# riffleito-KAP-REVA.net
KiCad netlist of a schematic drawn in EAGLE
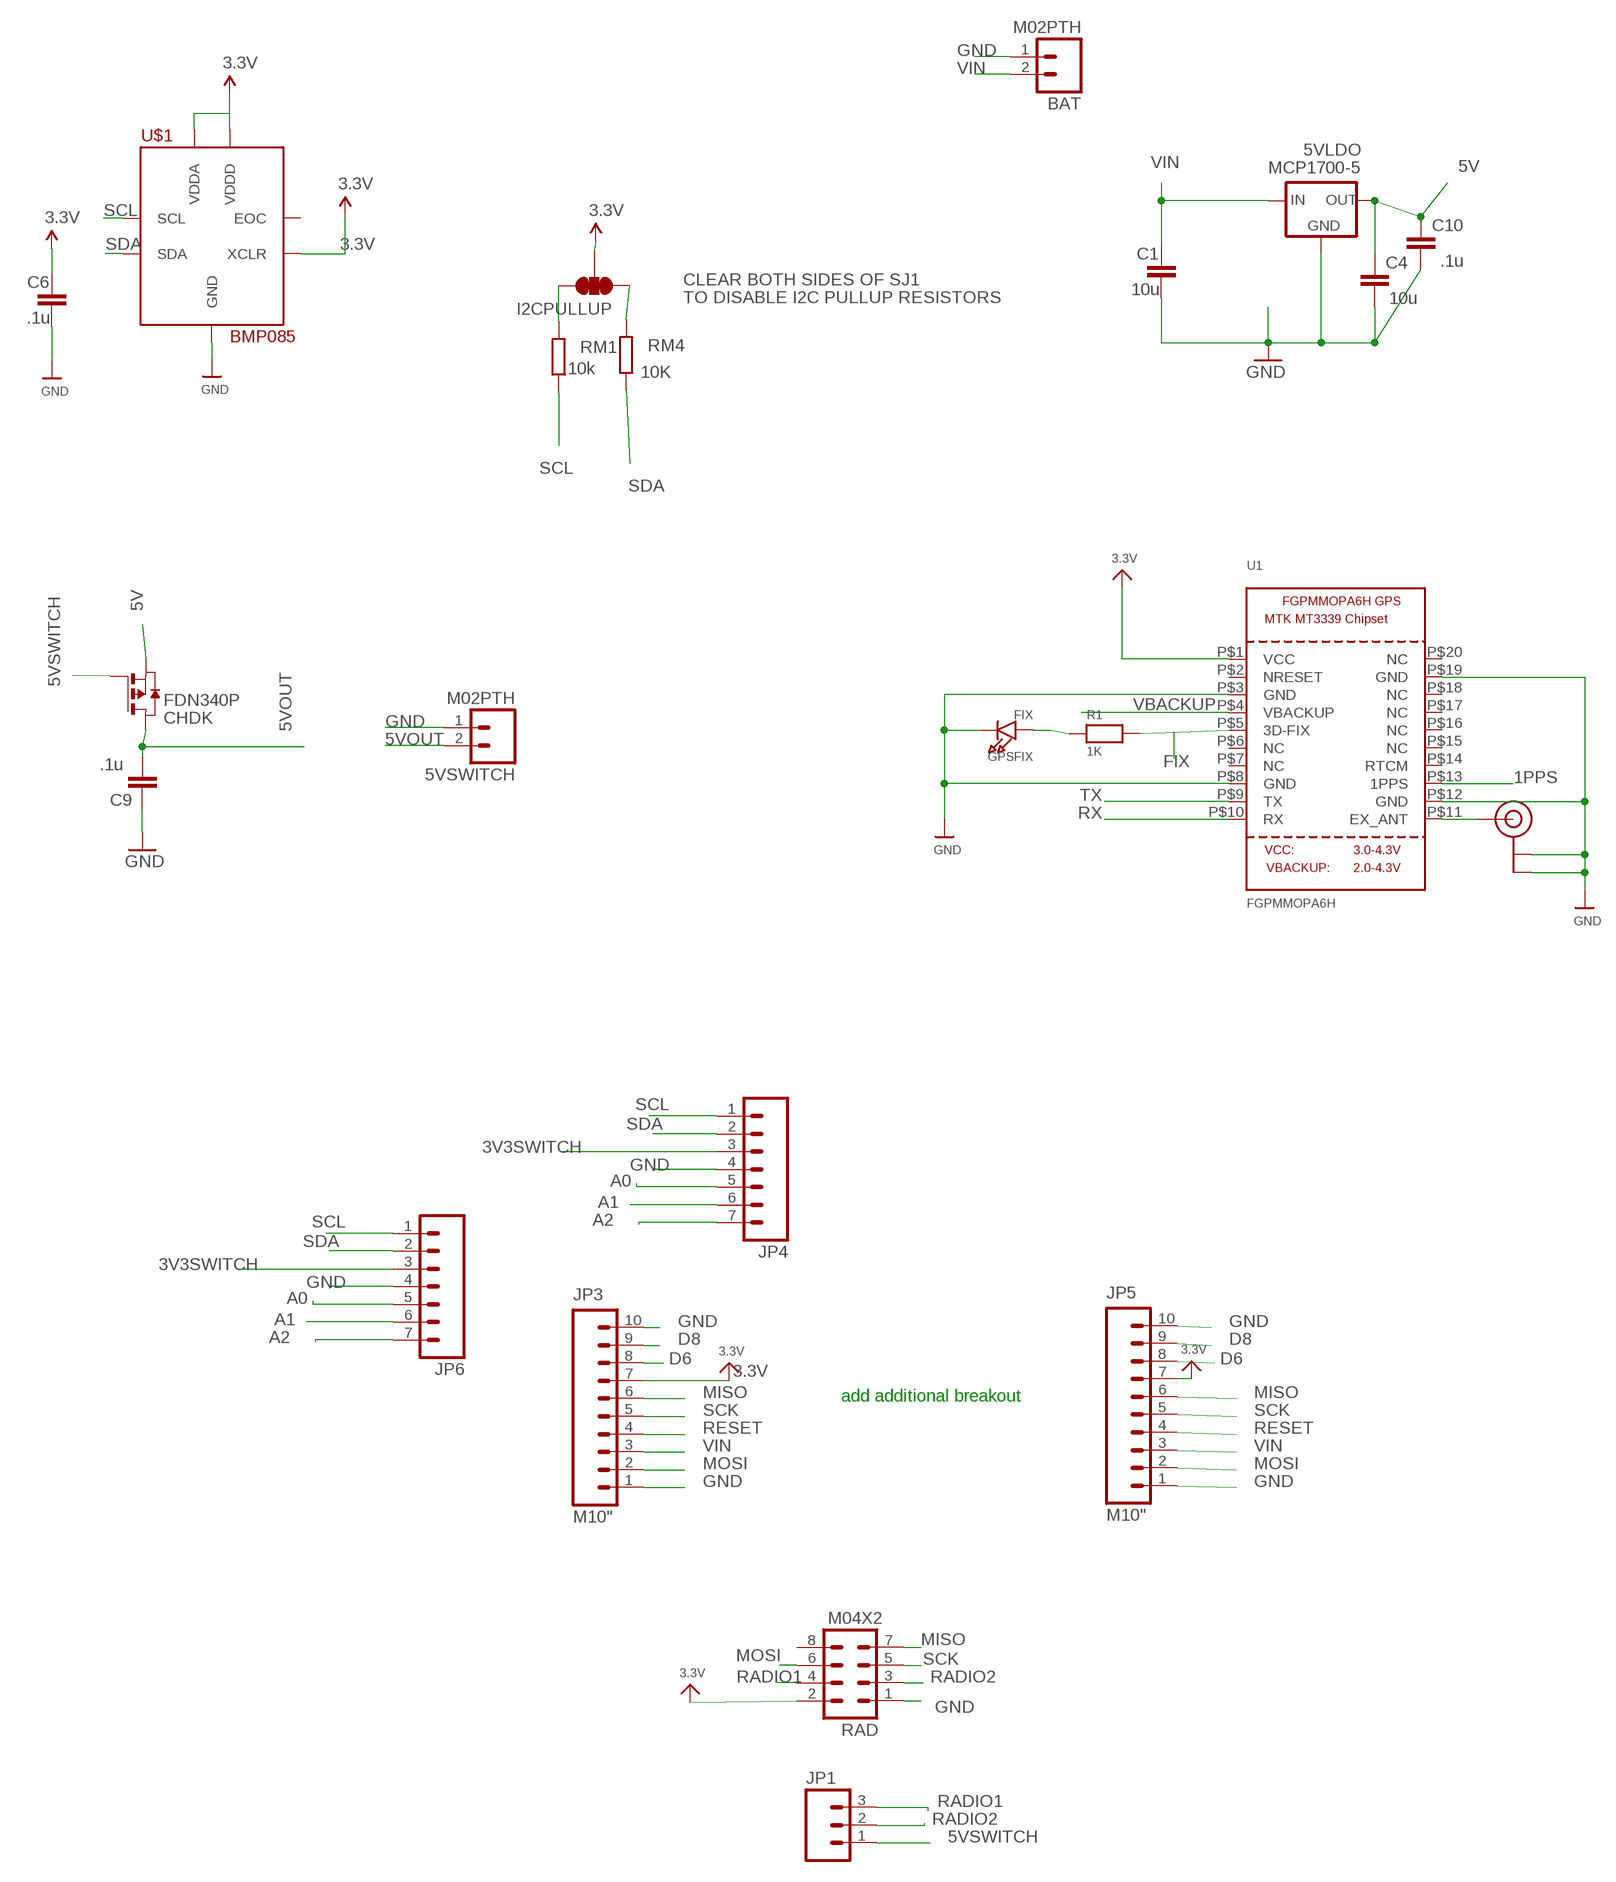
[diagram p0: schematic, sheet 1]

(export (version "E")
  (design (tool "Eeschema 10.0.6"))
  (components
    (comp (ref "5VLDO")
      (value "MCP1700-5")
      (footprint "eagle-import:SOT23")
      (libsource (lib "eagle-import") (part "MCP1700SOT233"))
    )
    (comp (ref "5VSWITCH")
      (value "M02PTH")
      (footprint "eagle-import:1X02")
      (libsource (lib "eagle-import") (part "M02PTH"))
    )
    (comp (ref "BAT")
      (value "M02PTH")
      (footprint "eagle-import:1X02")
      (libsource (lib "eagle-import") (part "M02PTH"))
    )
    (comp (ref "C1")
      (value "10u")
      (footprint "eagle-import:C0805")
      (libsource (lib "eagle-import") (part "C-EUC0805"))
    )
    (comp (ref "C4")
      (value "10u")
      (footprint "eagle-import:C0805")
      (libsource (lib "eagle-import") (part "C-EUC0805"))
    )
    (comp (ref "C6")
      (value ".1u")
      (footprint "eagle-import:C0805")
      (libsource (lib "eagle-import") (part "C-EUC0805"))
    )
    (comp (ref "C9")
      (value ".1u")
      (footprint "eagle-import:C0805")
      (libsource (lib "eagle-import") (part "C-EUC0805"))
    )
    (comp (ref "C10")
      (value ".1u")
      (footprint "eagle-import:C0805")
      (libsource (lib "eagle-import") (part "C-EUC0805"))
    )
    (comp (ref "CHDK")
      (value "FDN340P")
      (footprint "eagle-import:SOT-23")
      (libsource (lib "eagle-import") (part "PMOSSOT23"))
    )
    (comp (ref "GPSFIX")
      (value "FIX")
      (footprint "eagle-import:CHIPLED_0805")
      (libsource (lib "eagle-import") (part "LED0805"))
    )
    (comp (ref "I2CPULLUP")
      (value "SOLDERJUMPER_2WAYPASTE1&2&3")
      (footprint "eagle-import:SJ_3_PASTE1&2&3")
      (libsource (lib "eagle-import") (part "SOLDERJUMPER_2WAYPASTE1&2&3"))
    )
    (comp (ref "JP1")
      (value "M03PTH")
      (footprint "eagle-import:1X03")
      (libsource (lib "eagle-import") (part "M03PTH"))
    )
    (comp (ref "JP3")
      (value "M10\"")
      (footprint "eagle-import:1X10")
      (libsource (lib "eagle-import") (part "M10{dblquote}"))
    )
    (comp (ref "JP4")
      (value "M07")
      (footprint "eagle-import:1X07")
      (libsource (lib "eagle-import") (part "M07"))
    )
    (comp (ref "JP5")
      (value "M10\"")
      (footprint "eagle-import:1X10")
      (libsource (lib "eagle-import") (part "M10{dblquote}"))
    )
    (comp (ref "JP6")
      (value "M07")
      (footprint "eagle-import:1X07")
      (libsource (lib "eagle-import") (part "M07"))
    )
    (comp (ref "R1")
      (value "1K")
      (footprint "eagle-import:0805")
      (libsource (lib "eagle-import") (part "RESISTOR0805"))
    )
    (comp (ref "RAD")
      (value "M04X2")
      (footprint "eagle-import:2X4")
      (libsource (lib "eagle-import") (part "M04X2"))
    )
    (comp (ref "RM1")
      (value "10k")
      (footprint "eagle-import:R0805")
      (libsource (lib "eagle-import") (part "R-EU_R0805"))
    )
    (comp (ref "RM4")
      (value "10K")
      (footprint "eagle-import:R0805")
      (libsource (lib "eagle-import") (part "R-EU_R0805"))
    )
    (comp (ref "U$1")
      (value "BMP085")
      (footprint "eagle-import:BMP085")
      (libsource (lib "eagle-import") (part "BMP085"))
    )
    (comp (ref "U$20")
      (value "U.FL")
      (footprint "eagle-import:U.FL")
      (libsource (lib "eagle-import") (part "U.FL"))
    )
    (comp (ref "U1")
      (value "FGPMMOPA6H")
      (footprint "eagle-import:FGPMMOPA6H")
      (libsource (lib "eagle-import") (part "GPS_FGPMMOPA6H"))
    )
  )
  (nets
    (net (code "1") (name "/1PPS") (class "Default")
      (node (ref "U1") (pin "P$13") (pinfunction "1PPS_P$13") (pintype "bidirectional"))
    )
    (net (code "2") (name "/3V3SWITCH") (class "Default")
      (node (ref "JP4") (pin "3") (pinfunction "3_3") (pintype "passive"))
      (node (ref "JP6") (pin "3") (pinfunction "3_3") (pintype "passive"))
    )
    (net (code "3") (name "/5V") (class "Default")
      (node (ref "5VLDO") (pin "2") (pinfunction "OUT_2") (pintype "passive"))
      (node (ref "C10") (pin "1") (pinfunction "1_1") (pintype "passive"))
      (node (ref "C4") (pin "1") (pinfunction "1_1") (pintype "passive"))
      (node (ref "CHDK") (pin "2") (pinfunction "S_2") (pintype "passive"))
    )
    (net (code "4") (name "/5VOUT") (class "Default")
      (node (ref "5VSWITCH") (pin "2") (pinfunction "2_2") (pintype "passive"))
      (node (ref "C9") (pin "2") (pinfunction "2_2") (pintype "passive"))
      (node (ref "CHDK") (pin "1") (pinfunction "D_1") (pintype "passive"))
    )
    (net (code "5") (name "/5VSWITCH") (class "Default")
      (node (ref "CHDK") (pin "3") (pinfunction "G_3") (pintype "passive"))
      (node (ref "JP1") (pin "1") (pinfunction "1_1") (pintype "passive"))
    )
    (net (code "6") (name "/A0") (class "Default")
      (node (ref "JP4") (pin "5") (pinfunction "5_5") (pintype "passive"))
      (node (ref "JP6") (pin "5") (pinfunction "5_5") (pintype "passive"))
    )
    (net (code "7") (name "/A1") (class "Default")
      (node (ref "JP4") (pin "6") (pinfunction "6_6") (pintype "passive"))
      (node (ref "JP6") (pin "6") (pinfunction "6_6") (pintype "passive"))
    )
    (net (code "8") (name "/A2") (class "Default")
      (node (ref "JP4") (pin "7") (pinfunction "7_7") (pintype "passive"))
      (node (ref "JP6") (pin "7") (pinfunction "7_7") (pintype "passive"))
    )
    (net (code "9") (name "/D6") (class "Default")
      (node (ref "JP3") (pin "8") (pinfunction "8_8") (pintype "passive"))
      (node (ref "JP5") (pin "8") (pinfunction "8_8") (pintype "passive"))
    )
    (net (code "10") (name "/D8") (class "Default")
      (node (ref "JP3") (pin "9") (pinfunction "9_9") (pintype "passive"))
      (node (ref "JP5") (pin "9") (pinfunction "9_9") (pintype "passive"))
    )
    (net (code "12") (name "/MISO") (class "Default")
      (node (ref "JP3") (pin "6") (pinfunction "6_6") (pintype "passive"))
      (node (ref "JP5") (pin "6") (pinfunction "6_6") (pintype "passive"))
      (node (ref "RAD") (pin "7") (pinfunction "7_7") (pintype "passive"))
    )
    (net (code "13") (name "/MOSI") (class "Default")
      (node (ref "JP3") (pin "2") (pinfunction "2_2") (pintype "passive"))
      (node (ref "JP5") (pin "2") (pinfunction "2_2") (pintype "passive"))
      (node (ref "RAD") (pin "6") (pinfunction "6_6") (pintype "passive"))
    )
    (net (code "14") (name "/RADIO1") (class "Default")
      (node (ref "JP1") (pin "3") (pinfunction "3_3") (pintype "passive"))
      (node (ref "RAD") (pin "4") (pinfunction "4_4") (pintype "passive"))
    )
    (net (code "15") (name "/RADIO2") (class "Default")
      (node (ref "JP1") (pin "2") (pinfunction "2_2") (pintype "passive"))
      (node (ref "RAD") (pin "3") (pinfunction "3_3") (pintype "passive"))
    )
    (net (code "16") (name "/RESET") (class "Default")
      (node (ref "JP3") (pin "4") (pinfunction "4_4") (pintype "passive"))
      (node (ref "JP5") (pin "4") (pinfunction "4_4") (pintype "passive"))
    )
    (net (code "17") (name "/RX") (class "Default")
      (node (ref "U1") (pin "P$10") (pinfunction "RX_P$10") (pintype "bidirectional"))
    )
    (net (code "18") (name "/SCK") (class "Default")
      (node (ref "JP3") (pin "5") (pinfunction "5_5") (pintype "passive"))
      (node (ref "JP5") (pin "5") (pinfunction "5_5") (pintype "passive"))
      (node (ref "RAD") (pin "5") (pinfunction "5_5") (pintype "passive"))
    )
    (net (code "19") (name "/SCL") (class "Default")
      (node (ref "JP4") (pin "1") (pinfunction "1_1") (pintype "passive"))
      (node (ref "JP6") (pin "1") (pinfunction "1_1") (pintype "passive"))
      (node (ref "RM1") (pin "1") (pinfunction "1_1") (pintype "passive"))
      (node (ref "U$1") (pin "P$6") (pinfunction "SCL_P$6") (pintype "bidirectional"))
    )
    (net (code "20") (name "/SDA") (class "Default")
      (node (ref "JP4") (pin "2") (pinfunction "2_2") (pintype "passive"))
      (node (ref "JP6") (pin "2") (pinfunction "2_2") (pintype "passive"))
      (node (ref "RM4") (pin "1") (pinfunction "1_1") (pintype "passive"))
      (node (ref "U$1") (pin "P$7") (pinfunction "SDA_P$7") (pintype "bidirectional"))
    )
    (net (code "21") (name "/TX") (class "Default")
      (node (ref "U1") (pin "P$9") (pinfunction "TX_P$9") (pintype "bidirectional"))
    )
    (net (code "22") (name "/VBACKUP") (class "Default")
      (node (ref "U1") (pin "P$4") (pinfunction "VBACKUP_P$4") (pintype "bidirectional"))
    )
    (net (code "23") (name "/VIN") (class "Default")
      (node (ref "5VLDO") (pin "3") (pinfunction "IN_3") (pintype "input"))
      (node (ref "BAT") (pin "2") (pinfunction "2_2") (pintype "passive"))
      (node (ref "C1") (pin "1") (pinfunction "1_1") (pintype "passive"))
      (node (ref "JP3") (pin "3") (pinfunction "3_3") (pintype "passive"))
      (node (ref "JP5") (pin "3") (pinfunction "3_3") (pintype "passive"))
    )
    (net (code "24") (name "3.3V") (class "Default")
      (node (ref "C6") (pin "1") (pinfunction "1_1") (pintype "passive"))
      (node (ref "I2CPULLUP") (pin "2") (pinfunction "2_2") (pintype "passive"))
      (node (ref "JP3") (pin "7") (pinfunction "7_7") (pintype "passive"))
      (node (ref "JP5") (pin "7") (pinfunction "7_7") (pintype "passive"))
      (node (ref "RAD") (pin "2") (pinfunction "2_2") (pintype "passive"))
      (node (ref "U$1") (pin "P$3") (pinfunction "VDDA_P$3") (pintype "bidirectional"))
      (node (ref "U$1") (pin "P$4") (pinfunction "VDDD_P$4") (pintype "bidirectional"))
      (node (ref "U$1") (pin "P$8") (pinfunction "XCLR_P$8") (pintype "bidirectional"))
      (node (ref "U1") (pin "P$1") (pinfunction "VCC_P$1") (pintype "bidirectional"))
    )
    (net (code "25") (name "GND") (class "Default")
      (node (ref "5VLDO") (pin "1") (pinfunction "GND_1") (pintype "input"))
      (node (ref "5VSWITCH") (pin "1") (pinfunction "1_1") (pintype "passive"))
      (node (ref "BAT") (pin "1") (pinfunction "1_1") (pintype "passive"))
      (node (ref "C1") (pin "2") (pinfunction "2_2") (pintype "passive"))
      (node (ref "C10") (pin "2") (pinfunction "2_2") (pintype "passive"))
      (node (ref "C4") (pin "2") (pinfunction "2_2") (pintype "passive"))
      (node (ref "C6") (pin "2") (pinfunction "2_2") (pintype "passive"))
      (node (ref "C9") (pin "1") (pinfunction "1_1") (pintype "passive"))
      (node (ref "GPSFIX") (pin "C") (pinfunction "C_C") (pintype "passive"))
      (node (ref "JP3") (pin "1") (pinfunction "1_1") (pintype "passive"))
      (node (ref "JP3") (pin "10") (pinfunction "10_10") (pintype "passive"))
      (node (ref "JP4") (pin "4") (pinfunction "4_4") (pintype "passive"))
      (node (ref "JP5") (pin "1") (pinfunction "1_1") (pintype "passive"))
      (node (ref "JP5") (pin "10") (pinfunction "10_10") (pintype "passive"))
      (node (ref "JP6") (pin "4") (pinfunction "4_4") (pintype "passive"))
      (node (ref "RAD") (pin "1") (pinfunction "1_1") (pintype "passive"))
      (node (ref "U$1") (pin "P$1") (pinfunction "GND_P$1") (pintype "power_in"))
      (node (ref "U$20") (pin "P$1") (pinfunction "GND_P$1") (pintype "bidirectional"))
      (node (ref "U$20") (pin "P$2") (pinfunction "GND_P$2") (pintype "bidirectional"))
      (node (ref "U1") (pin "P$12") (pinfunction "GND_P$12") (pintype "bidirectional"))
      (node (ref "U1") (pin "P$19") (pinfunction "GND_P$19") (pintype "bidirectional"))
      (node (ref "U1") (pin "P$3") (pinfunction "GND_P$3") (pintype "bidirectional"))
      (node (ref "U1") (pin "P$8") (pinfunction "GND_P$8") (pintype "bidirectional"))
    )
    (net (code "26") (name "Net-(GPSFIX-PadA)") (class "Default")
      (node (ref "GPSFIX") (pin "A") (pinfunction "A_A") (pintype "passive"))
      (node (ref "R1") (pin "1") (pinfunction "1_1") (pintype "passive"))
    )
    (net (code "27") (name "Net-(I2CPULLUP-Pad1)") (class "Default")
      (node (ref "I2CPULLUP") (pin "1") (pinfunction "1_1") (pintype "passive"))
      (node (ref "RM4") (pin "2") (pinfunction "2_2") (pintype "passive"))
    )
    (net (code "28") (name "Net-(I2CPULLUP-Pad3)") (class "Default")
      (node (ref "I2CPULLUP") (pin "3") (pinfunction "3_3") (pintype "passive"))
      (node (ref "RM1") (pin "2") (pinfunction "2_2") (pintype "passive"))
    )
    (net (code "29") (name "Net-(U$20-SIGNAL)") (class "Default")
      (node (ref "U$20") (pin "P$3") (pinfunction "SIGNAL_P$3") (pintype "bidirectional"))
      (node (ref "U1") (pin "P$11") (pinfunction "EX_ANT_P$11") (pintype "bidirectional"))
    )
    (net (code "30") (name "Net-(U1-3D-FIX)") (class "Default")
      (node (ref "R1") (pin "2") (pinfunction "2_2") (pintype "passive"))
      (node (ref "U1") (pin "P$5") (pinfunction "3D-FIX_P$5") (pintype "bidirectional"))
    )
    (net (code "31") (name "unconnected-(RAD-Pad8)") (class "Default")
      (node (ref "RAD") (pin "8") (pinfunction "8_8") (pintype "passive"))
    )
    (net (code "32") (name "unconnected-(U$1-EOC-PadP$2)") (class "Default")
      (node (ref "U$1") (pin "P$2") (pinfunction "EOC_P$2") (pintype "bidirectional"))
    )
    (net (code "33") (name "unconnected-(U1-NC-PadP$6)") (class "Default")
      (node (ref "U1") (pin "P$6") (pinfunction "NC_P$6") (pintype "bidirectional"))
    )
    (net (code "34") (name "unconnected-(U1-NC-PadP$7)") (class "Default")
      (node (ref "U1") (pin "P$7") (pinfunction "NC_P$7") (pintype "bidirectional"))
    )
    (net (code "35") (name "unconnected-(U1-NC-PadP$15)") (class "Default")
      (node (ref "U1") (pin "P$15") (pinfunction "NC_P$15") (pintype "bidirectional"))
    )
    (net (code "36") (name "unconnected-(U1-NC-PadP$16)") (class "Default")
      (node (ref "U1") (pin "P$16") (pinfunction "NC_P$16") (pintype "bidirectional"))
    )
    (net (code "37") (name "unconnected-(U1-NC-PadP$17)") (class "Default")
      (node (ref "U1") (pin "P$17") (pinfunction "NC_P$17") (pintype "bidirectional"))
    )
    (net (code "38") (name "unconnected-(U1-NC-PadP$18)") (class "Default")
      (node (ref "U1") (pin "P$18") (pinfunction "NC_P$18") (pintype "bidirectional"))
    )
    (net (code "39") (name "unconnected-(U1-NC-PadP$20)") (class "Default")
      (node (ref "U1") (pin "P$20") (pinfunction "NC_P$20") (pintype "bidirectional"))
    )
    (net (code "40") (name "unconnected-(U1-NRESET-PadP$2)") (class "Default")
      (node (ref "U1") (pin "P$2") (pinfunction "NRESET_P$2") (pintype "bidirectional"))
    )
    (net (code "41") (name "unconnected-(U1-RTCM-PadP$14)") (class "Default")
      (node (ref "U1") (pin "P$14") (pinfunction "RTCM_P$14") (pintype "bidirectional"))
    )
  )
)
